# Grove-Relay-v1_2.net
KiCad netlist of a schematic drawn in EAGLE
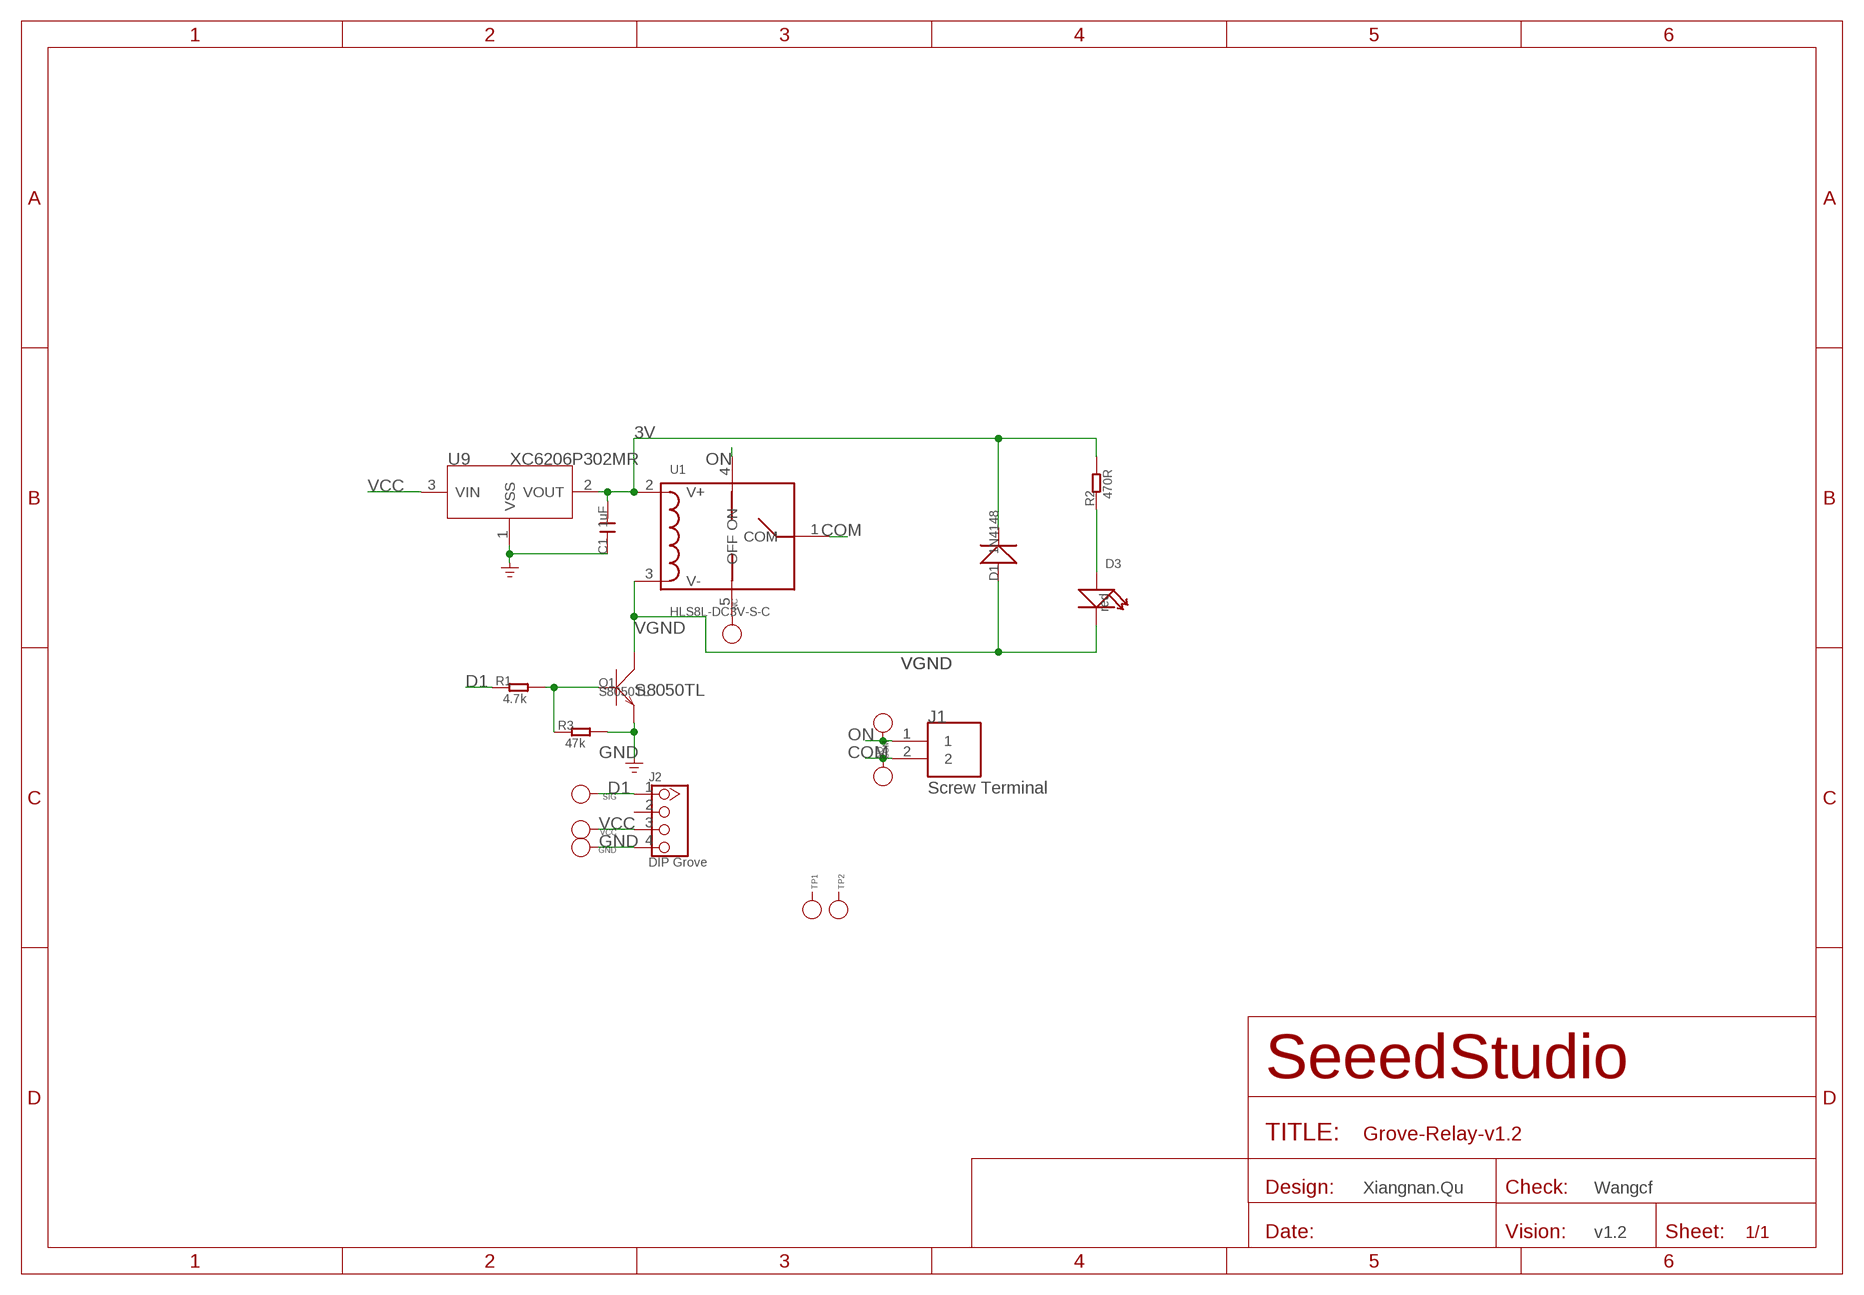
[diagram p0: schematic, sheet 1]

(export (version "E")
  (design (tool "Eeschema 10.0.6"))
  (components
    (comp (ref "C1")
      (value "1uF")
      (footprint "eagle-import:C0603")
      (libsource (lib "eagle-import") (part "C-0603"))
    )
    (comp (ref "COM")
      (value "PAD-TEST-POINT'4545'")
      (footprint "eagle-import:TP_4545")
      (fields (field (name "PARTNO") "DNP"))
      (libsource (lib "eagle-import") (part "PAD-TEST-POINT'4545'"))
    )
    (comp (ref "D1")
      (value "1N4148")
      (footprint "eagle-import:LL-34")
      (libsource (lib "eagle-import") (part "D'1N4148-SMD'"))
    )
    (comp (ref "D3")
      (value "red")
      (footprint "eagle-import:LED-0603")
      (libsource (lib "eagle-import") (part "LED'0603'"))
    )
    (comp (ref "GND")
      (value "PAD-TEST-POINT'4545'")
      (footprint "eagle-import:TP_4545")
      (fields (field (name "PARTNO") "DNP"))
      (libsource (lib "eagle-import") (part "PAD-TEST-POINT'4545'"))
    )
    (comp (ref "J1")
      (value "Screw Terminal")
      (footprint "eagle-import:CON2")
      (libsource (lib "eagle-import") (part "CON2"))
    )
    (comp (ref "J2")
      (value "DIP Grove")
      (footprint "eagle-import:2.0_1X4")
      (libsource (lib "eagle-import") (part "TWIG_2.0"))
    )
    (comp (ref "NC")
      (value "PAD-TEST-POINT'4545'")
      (footprint "eagle-import:TP_4545")
      (fields (field (name "PARTNO") "DNP"))
      (libsource (lib "eagle-import") (part "PAD-TEST-POINT'4545'"))
    )
    (comp (ref "NO")
      (value "PAD-TEST-POINT'4545'")
      (footprint "eagle-import:TP_4545")
      (fields (field (name "PARTNO") "DNP"))
      (libsource (lib "eagle-import") (part "PAD-TEST-POINT'4545'"))
    )
    (comp (ref "Q1")
      (value "S8050TL")
      (footprint "eagle-import:SOT23")
      (libsource (lib "eagle-import") (part "TRANSISTOR-NPN-SOT23"))
    )
    (comp (ref "R1")
      (value "4.7k")
      (footprint "eagle-import:R0603")
      (libsource (lib "eagle-import") (part "R-0603"))
    )
    (comp (ref "R2")
      (value "470R")
      (footprint "eagle-import:R0603")
      (libsource (lib "eagle-import") (part "R-0603"))
    )
    (comp (ref "R3")
      (value "47k")
      (footprint "eagle-import:R0603")
      (libsource (lib "eagle-import") (part "R-0603"))
    )
    (comp (ref "SIG")
      (value "PAD-TEST-POINT'4545'")
      (footprint "eagle-import:TP_4545")
      (fields (field (name "PARTNO") "DNP"))
      (libsource (lib "eagle-import") (part "PAD-TEST-POINT'4545'"))
    )
    (comp (ref "TP1")
      (value "PAD-TEST-POINT'4545'")
      (footprint "eagle-import:TP_4545")
      (fields (field (name "PARTNO") "DNP"))
      (libsource (lib "eagle-import") (part "PAD-TEST-POINT'4545'"))
    )
    (comp (ref "TP2")
      (value "PAD-TEST-POINT'4545'")
      (footprint "eagle-import:TP_4545")
      (fields (field (name "PARTNO") "DNP"))
      (libsource (lib "eagle-import") (part "PAD-TEST-POINT'4545'"))
    )
    (comp (ref "U1")
      (value "HLS8L-DC3V-S-C")
      (footprint "eagle-import:RELAY")
      (libsource (lib "eagle-import") (part "RELAY"))
    )
    (comp (ref "U9")
      (value "XC6206P302MR")
      (footprint "eagle-import:SOT23")
      (libsource (lib "eagle-import") (part "XC6206MR"))
    )
    (comp (ref "VCC")
      (value "PAD-TEST-POINT'4545'")
      (footprint "eagle-import:TP_4545")
      (fields (field (name "PARTNO") "DNP"))
      (libsource (lib "eagle-import") (part "PAD-TEST-POINT'4545'"))
    )
  )
  (nets
    (net (code "1") (name "/3V") (class "Default")
      (node (ref "C1") (pin "2") (pinfunction "2_2") (pintype "passive"))
      (node (ref "D1") (pin "C") (pinfunction "-_C") (pintype "passive"))
      (node (ref "R2") (pin "2") (pinfunction "2_2") (pintype "passive"))
      (node (ref "U1") (pin "2") (pinfunction "V+_2") (pintype "bidirectional"))
      (node (ref "U9") (pin "2") (pinfunction "VOUT_2") (pintype "output"))
    )
    (net (code "2") (name "/COM") (class "Default")
      (node (ref "COM") (pin "T") (pinfunction "T_T") (pintype "bidirectional"))
      (node (ref "J1") (pin "2") (pinfunction "2_2") (pintype "bidirectional"))
      (node (ref "U1") (pin "1") (pinfunction "COM_1") (pintype "bidirectional"))
    )
    (net (code "3") (name "/D1") (class "Default")
      (node (ref "J2") (pin "1") (pinfunction "1_1") (pintype "bidirectional"))
      (node (ref "R1") (pin "1") (pinfunction "1_1") (pintype "passive"))
      (node (ref "SIG") (pin "T") (pinfunction "T_T") (pintype "bidirectional"))
    )
    (net (code "4") (name "/ON") (class "Default")
      (node (ref "J1") (pin "1") (pinfunction "1_1") (pintype "bidirectional"))
      (node (ref "NO") (pin "T") (pinfunction "T_T") (pintype "bidirectional"))
      (node (ref "U1") (pin "4") (pinfunction "ON_4") (pintype "bidirectional"))
    )
    (net (code "5") (name "/VCC") (class "Default")
      (node (ref "J2") (pin "3") (pinfunction "3_3") (pintype "bidirectional"))
      (node (ref "U9") (pin "3") (pinfunction "VIN_3") (pintype "input"))
      (node (ref "VCC") (pin "T") (pinfunction "T_T") (pintype "bidirectional"))
    )
    (net (code "6") (name "/VGND") (class "Default")
      (node (ref "D1") (pin "A") (pinfunction "+_A") (pintype "passive"))
      (node (ref "D3") (pin "-") (pinfunction "-_-") (pintype "passive"))
      (node (ref "Q1") (pin "3") (pinfunction "C_3") (pintype "passive"))
      (node (ref "U1") (pin "3") (pinfunction "V-_3") (pintype "bidirectional"))
    )
    (net (code "7") (name "GND_POWER") (class "Default")
      (node (ref "C1") (pin "1") (pinfunction "1_1") (pintype "passive"))
      (node (ref "GND") (pin "T") (pinfunction "T_T") (pintype "bidirectional"))
      (node (ref "J2") (pin "4") (pinfunction "4_4") (pintype "bidirectional"))
      (node (ref "Q1") (pin "2") (pinfunction "E_2") (pintype "passive"))
      (node (ref "R3") (pin "2") (pinfunction "2_2") (pintype "passive"))
      (node (ref "U9") (pin "1") (pinfunction "VSS_1") (pintype "power_in"))
    )
    (net (code "8") (name "Net-(D3-Pad+)") (class "Default")
      (node (ref "D3") (pin "+") (pinfunction "+_+") (pintype "passive"))
      (node (ref "R2") (pin "1") (pinfunction "1_1") (pintype "passive"))
    )
    (net (code "9") (name "Net-(Q1-B)") (class "Default")
      (node (ref "Q1") (pin "1") (pinfunction "B_1") (pintype "passive"))
      (node (ref "R1") (pin "2") (pinfunction "2_2") (pintype "passive"))
      (node (ref "R3") (pin "1") (pinfunction "1_1") (pintype "passive"))
    )
    (net (code "10") (name "Net-(U1-OFF)") (class "Default")
      (node (ref "NC") (pin "T") (pinfunction "T_T") (pintype "bidirectional"))
      (node (ref "U1") (pin "5") (pinfunction "OFF_5") (pintype "bidirectional"))
    )
    (net (code "11") (name "unconnected-(J2-Pad2)") (class "Default")
      (node (ref "J2") (pin "2") (pinfunction "2_2") (pintype "bidirectional"))
    )
    (net (code "12") (name "unconnected-(TP1-PadT)") (class "Default")
      (node (ref "TP1") (pin "T") (pinfunction "T_T") (pintype "bidirectional"))
    )
    (net (code "13") (name "unconnected-(TP2-PadT)") (class "Default")
      (node (ref "TP2") (pin "T") (pinfunction "T_T") (pintype "bidirectional"))
    )
  )
)
